# SparkFun-ESP8266-Development-Board.net
KiCad netlist of a schematic drawn in EAGLE
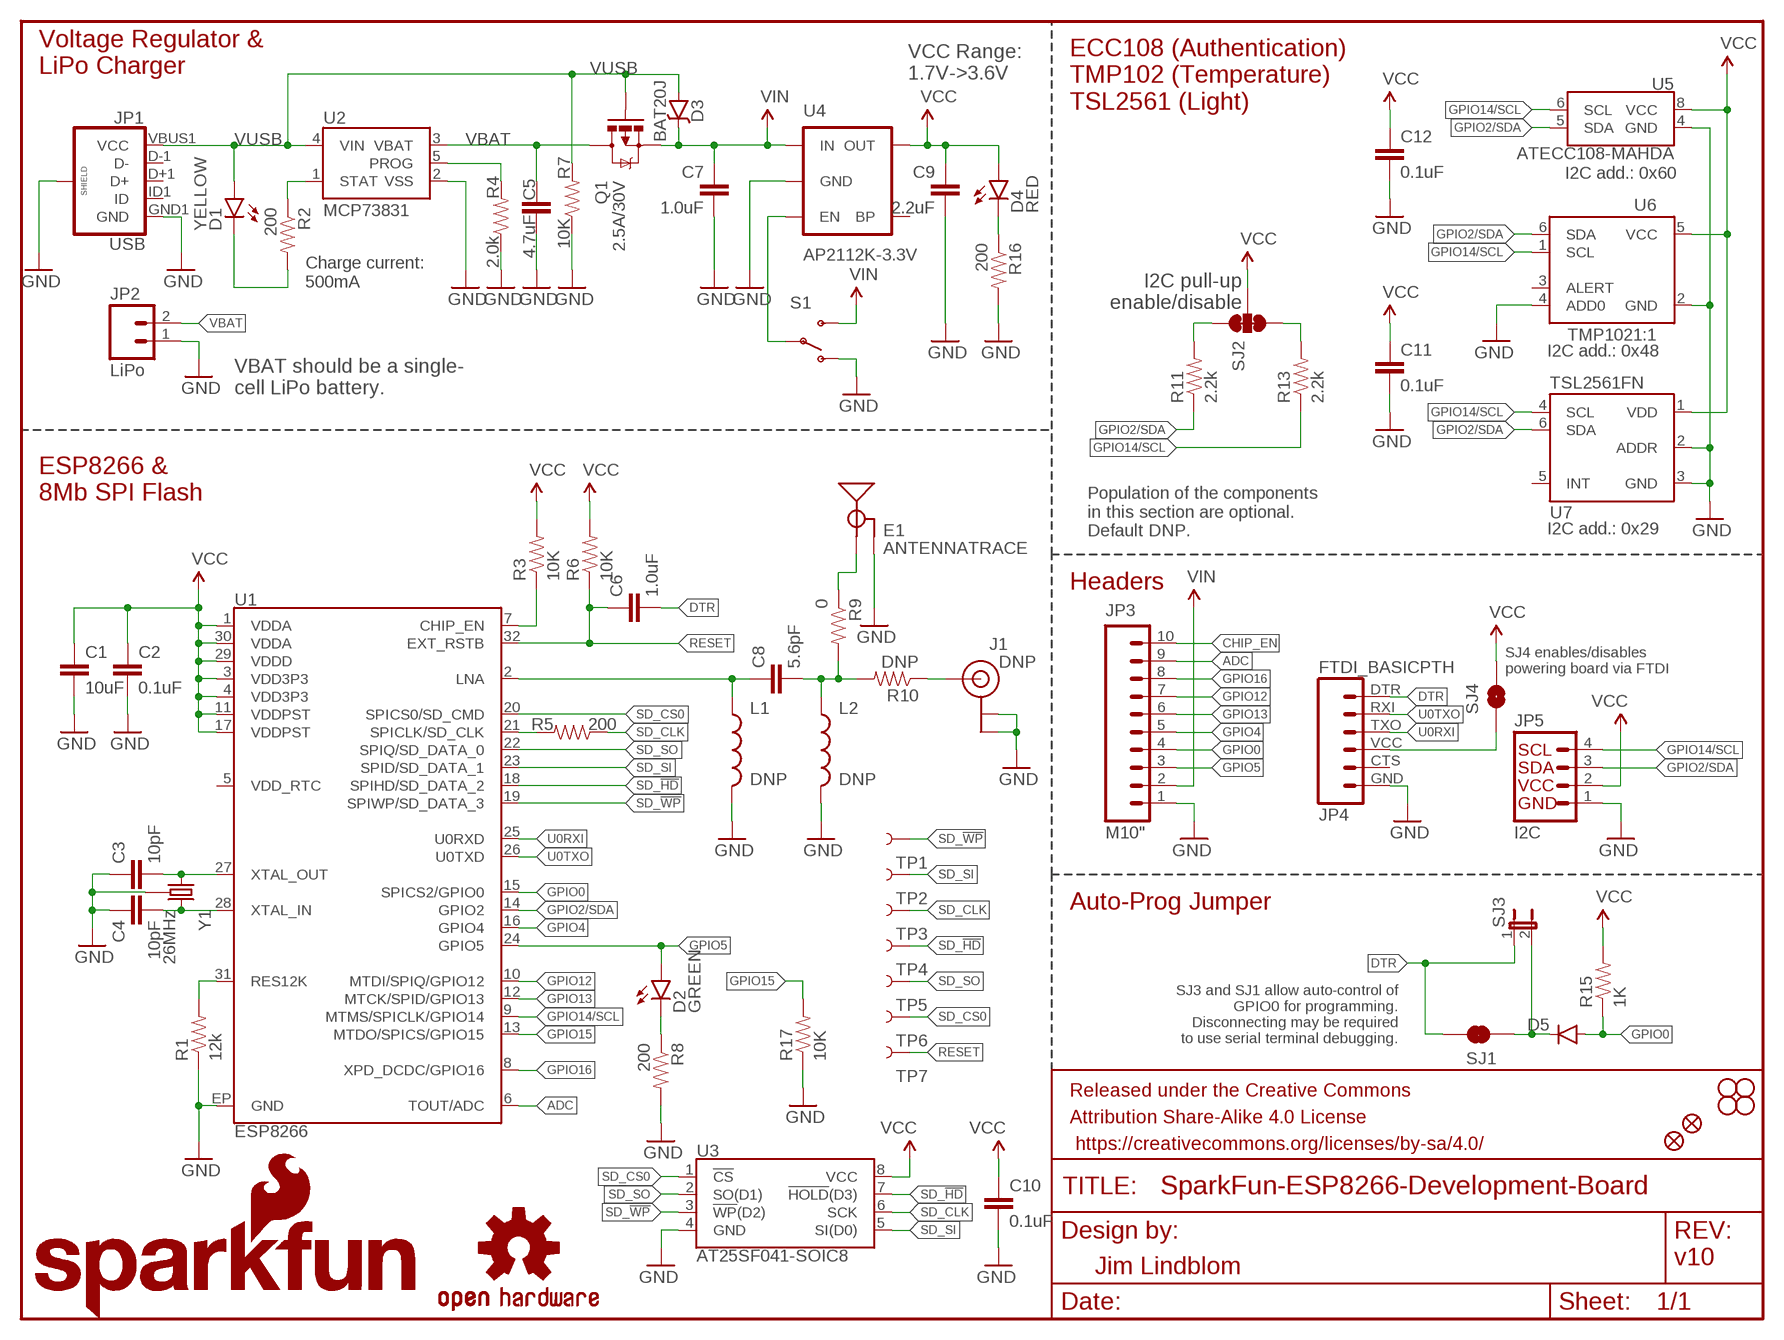
[diagram p0: schematic, sheet 1]

(export (version "E")
  (design (tool "Eeschema 10.0.6"))
  (components
    (comp (ref "C1")
      (value "10uF")
      (footprint "eagle-import:0603-CAP")
      (libsource (lib "eagle-import") (part "10UF-6.3V-20%(0603)"))
    )
    (comp (ref "C2")
      (value "0.1uF")
      (footprint "eagle-import:0603-CAP")
      (libsource (lib "eagle-import") (part "0.1UF-25V(+80/-20%)(0603)"))
    )
    (comp (ref "C3")
      (value "10pF")
      (footprint "eagle-import:0603-CAP")
      (libsource (lib "eagle-import") (part "10PF-50V-5%(0603)"))
    )
    (comp (ref "C4")
      (value "10pF")
      (footprint "eagle-import:0603-CAP")
      (libsource (lib "eagle-import") (part "10PF-50V-5%(0603)"))
    )
    (comp (ref "C5")
      (value "4.7uF")
      (footprint "eagle-import:0603-CAP")
      (libsource (lib "eagle-import") (part "4.7UF-6.3V-10%(0603)0603"))
    )
    (comp (ref "C6")
      (value "1.0uF")
      (footprint "eagle-import:0603-CAP")
      (libsource (lib "eagle-import") (part "1.0UF-16V-10%(0603)"))
    )
    (comp (ref "C7")
      (value "1.0uF")
      (footprint "eagle-import:0805")
      (libsource (lib "eagle-import") (part "1.0UF-25V-+80/-20(0805)"))
    )
    (comp (ref "C8")
      (value "5.6pF")
      (footprint "eagle-import:0603-CAP")
      (libsource (lib "eagle-import") (part "CAP0603-CAP"))
    )
    (comp (ref "C9")
      (value "2.2uF")
      (footprint "eagle-import:0603-CAP")
      (libsource (lib "eagle-import") (part "2.2UF-10V-20%(0603)"))
    )
    (comp (ref "C10")
      (value "0.1uF")
      (footprint "eagle-import:0603-CAP")
      (libsource (lib "eagle-import") (part "0.1UF-25V(+80/-20%)(0603)"))
    )
    (comp (ref "C11")
      (value "0.1uF")
      (footprint "eagle-import:0603-CAP")
      (libsource (lib "eagle-import") (part "0.1UF-25V(+80/-20%)(0603)"))
    )
    (comp (ref "C12")
      (value "0.1uF")
      (footprint "eagle-import:0603-CAP")
      (libsource (lib "eagle-import") (part "0.1UF-25V(+80/-20%)(0603)"))
    )
    (comp (ref "D1")
      (value "YELLOW")
      (footprint "eagle-import:LED-0603")
      (libsource (lib "eagle-import") (part "LED-YELLOW0603"))
    )
    (comp (ref "D2")
      (value "GREEN")
      (footprint "eagle-import:LED-0603")
      (libsource (lib "eagle-import") (part "LED-GREEN0603"))
    )
    (comp (ref "D3")
      (value "BAT20J")
      (footprint "eagle-import:SOD-323")
      (libsource (lib "eagle-import") (part "DIODE-SCHOTTKY-BAT20J"))
    )
    (comp (ref "D4")
      (value "RED")
      (footprint "eagle-import:LED-0603")
      (libsource (lib "eagle-import") (part "LED-RED0603"))
    )
    (comp (ref "D5")
      (value "DIODEBAS16")
      (footprint "eagle-import:SOD-323")
      (libsource (lib "eagle-import") (part "DIODEBAS16"))
    )
    (comp (ref "E1")
      (value "ANTENNATRACE")
      (footprint "eagle-import:TRACE_ANTENNA_2.4GHZ_25.7MM")
      (libsource (lib "eagle-import") (part "ANTENNATRACE"))
    )
    (comp (ref "FID1")
      (value "FIDUCIAL1X2")
      (footprint "eagle-import:FIDUCIAL-1X2")
      (libsource (lib "eagle-import") (part "FIDUCIAL1X2"))
    )
    (comp (ref "FID2")
      (value "FIDUCIAL1X2")
      (footprint "eagle-import:FIDUCIAL-1X2")
      (libsource (lib "eagle-import") (part "FIDUCIAL1X2"))
    )
    (comp (ref "FRAME1")
      (value "FRAME-LETTER")
      (footprint "eagle-import:CREATIVE_COMMONS")
      (libsource (lib "eagle-import") (part "FRAME-LETTER"))
    )
    (comp (ref "J1")
      (value "DNP")
      (footprint "eagle-import:U.FL")
      (libsource (lib "eagle-import") (part "U.FL"))
    )
    (comp (ref "JP1")
      (value "USB")
      (footprint "eagle-import:USB-B-MICRO-SMD_V03")
      (libsource (lib "eagle-import") (part "USB_MICROB_PLUGCONN-11752"))
    )
    (comp (ref "JP2")
      (value "LiPo")
      (footprint "eagle-import:JST-2-PTH")
      (libsource (lib "eagle-import") (part "M02JST-PTH-2"))
    )
    (comp (ref "JP3")
      (value "M10\"")
      (footprint "eagle-import:1X10")
      (libsource (lib "eagle-import") (part "M10{dblquote}"))
    )
    (comp (ref "JP4")
      (value "FTDI_BASICPTH")
      (footprint "eagle-import:FTDI_BASIC")
      (libsource (lib "eagle-import") (part "FTDI_BASICPTH"))
    )
    (comp (ref "JP5")
      (value "I2C")
      (footprint "eagle-import:1X04")
      (libsource (lib "eagle-import") (part "I2C_STANDARD"))
    )
    (comp (ref "L1")
      (value "DNP")
      (footprint "eagle-import:0603")
      (libsource (lib "eagle-import") (part "INDUCTOR0603"))
    )
    (comp (ref "L2")
      (value "DNP")
      (footprint "eagle-import:0603")
      (libsource (lib "eagle-import") (part "INDUCTOR0603"))
    )
    (comp (ref "LOGO1")
      (value "SFE_LOGO_NAME.2_INCH")
      (footprint "eagle-import:SFE_LOGO_NAME_.2")
      (libsource (lib "eagle-import") (part "SFE_LOGO_NAME.2_INCH"))
    )
    (comp (ref "LOGO3")
      (value "SFE_LOGO_FLAME.1_INCH")
      (footprint "eagle-import:SFE_LOGO_FLAME_.1")
      (libsource (lib "eagle-import") (part "SFE_LOGO_FLAME.1_INCH"))
    )
    (comp (ref "LOGO4")
      (value "OSHW-LOGOS")
      (footprint "eagle-import:OSHW-LOGO-S")
      (libsource (lib "eagle-import") (part "OSHW-LOGOS"))
    )
    (comp (ref "Q1")
      (value "2.5A/30V")
      (footprint "eagle-import:SOT23-3")
      (libsource (lib "eagle-import") (part "MOSFET-PCHANNELDMG2307L"))
    )
    (comp (ref "R1")
      (value "12k")
      (footprint "eagle-import:0603-RES")
      (libsource (lib "eagle-import") (part "12KOHM-1/10W-1%(0603)"))
    )
    (comp (ref "R2")
      (value "200")
      (footprint "eagle-import:0603-RES")
      (libsource (lib "eagle-import") (part "200OHM1/10W1%(0603)"))
    )
    (comp (ref "R3")
      (value "10K")
      (footprint "eagle-import:0603-RES")
      (libsource (lib "eagle-import") (part "10KOHM1/10W1%(0603)0603"))
    )
    (comp (ref "R4")
      (value "2.0k")
      (footprint "eagle-import:0603-RES")
      (libsource (lib "eagle-import") (part "2.0KOHM1/10W5%(0603)"))
    )
    (comp (ref "R5")
      (value "200")
      (footprint "eagle-import:0603-RES")
      (libsource (lib "eagle-import") (part "200OHM1/10W1%(0603)"))
    )
    (comp (ref "R6")
      (value "10K")
      (footprint "eagle-import:0603-RES")
      (libsource (lib "eagle-import") (part "10KOHM1/10W1%(0603)0603"))
    )
    (comp (ref "R7")
      (value "10K")
      (footprint "eagle-import:0603-RES")
      (libsource (lib "eagle-import") (part "10KOHM1/10W1%(0603)0603"))
    )
    (comp (ref "R8")
      (value "200")
      (footprint "eagle-import:0603-RES")
      (libsource (lib "eagle-import") (part "200OHM1/10W1%(0603)"))
    )
    (comp (ref "R9")
      (value "0")
      (footprint "eagle-import:0603")
      (libsource (lib "eagle-import") (part "0OHM1/10W5%(0603)"))
    )
    (comp (ref "R10")
      (value "DNP")
      (footprint "eagle-import:0603-RES")
      (libsource (lib "eagle-import") (part "RESISTOR0603-RES"))
    )
    (comp (ref "R11")
      (value "2.2k")
      (footprint "eagle-import:0603-RES")
      (libsource (lib "eagle-import") (part "2.2KOHM1/10W1%(0603)"))
    )
    (comp (ref "R13")
      (value "2.2k")
      (footprint "eagle-import:0603-RES")
      (libsource (lib "eagle-import") (part "2.2KOHM1/10W1%(0603)"))
    )
    (comp (ref "R15")
      (value "1K")
      (footprint "eagle-import:0603-RES")
      (libsource (lib "eagle-import") (part "1KOHM1/10W1%(0603)"))
    )
    (comp (ref "R16")
      (value "200")
      (footprint "eagle-import:0603-RES")
      (libsource (lib "eagle-import") (part "200OHM1/10W1%(0603)"))
    )
    (comp (ref "R17")
      (value "10K")
      (footprint "eagle-import:0603-RES")
      (libsource (lib "eagle-import") (part "10KOHM1/10W1%(0603)0603"))
    )
    (comp (ref "S1")
      (value "SWITCH-SPDT-SMD-A")
      (footprint "eagle-import:SWITCH-SPST-SMD-A")
      (libsource (lib "eagle-import") (part "SWITCH-SPDT-SMD-A"))
    )
    (comp (ref "SJ1")
      (value "JUMPER-PAD-2-NC_BY_TRACE")
      (footprint "eagle-import:PAD-JUMPER-2-NC_BY_TRACE_YES_SILK")
      (libsource (lib "eagle-import") (part "JUMPER-PAD-2-NC_BY_TRACE"))
    )
    (comp (ref "SJ2")
      (value "JUMPER-PAD-3-NC_BY_TRACE")
      (footprint "eagle-import:PAD-JUMPER-3-3OF3_NC_BY_TRACE_YES_SILK_FULL_BOX")
      (libsource (lib "eagle-import") (part "JUMPER-PAD-3-NC_BY_TRACE"))
    )
    (comp (ref "SJ3")
      (value "JUMPER-PTH-2-NC")
      (footprint "eagle-import:PTH-JUMPER-NC_BOTTOM_NO_SILK")
      (libsource (lib "eagle-import") (part "JUMPER-PTH-2-NC"))
    )
    (comp (ref "SJ4")
      (value "JUMPER-PAD-2-NOYES_SILK")
      (footprint "eagle-import:PAD-JUMPER-2-NO_YES_SILK")
      (libsource (lib "eagle-import") (part "JUMPER-PAD-2-NOYES_SILK"))
    )
    (comp (ref "STANDOFF1")
      (value "STAND-OFF")
      (footprint "eagle-import:STAND-OFF")
      (libsource (lib "eagle-import") (part "STAND-OFF"))
    )
    (comp (ref "STANDOFF2")
      (value "STAND-OFF")
      (footprint "eagle-import:STAND-OFF")
      (libsource (lib "eagle-import") (part "STAND-OFF"))
    )
    (comp (ref "STANDOFF3")
      (value "STAND-OFF")
      (footprint "eagle-import:STAND-OFF")
      (libsource (lib "eagle-import") (part "STAND-OFF"))
    )
    (comp (ref "STANDOFF4")
      (value "STAND-OFF")
      (footprint "eagle-import:STAND-OFF")
      (libsource (lib "eagle-import") (part "STAND-OFF"))
    )
    (comp (ref "TP1")
      (value "TEST-POINT3X5")
      (footprint "eagle-import:PAD.03X.05")
      (libsource (lib "eagle-import") (part "TEST-POINT3X5"))
    )
    (comp (ref "TP2")
      (value "TEST-POINT3X5")
      (footprint "eagle-import:PAD.03X.05")
      (libsource (lib "eagle-import") (part "TEST-POINT3X5"))
    )
    (comp (ref "TP3")
      (value "TEST-POINT3X5")
      (footprint "eagle-import:PAD.03X.05")
      (libsource (lib "eagle-import") (part "TEST-POINT3X5"))
    )
    (comp (ref "TP4")
      (value "TEST-POINT3X5")
      (footprint "eagle-import:PAD.03X.05")
      (libsource (lib "eagle-import") (part "TEST-POINT3X5"))
    )
    (comp (ref "TP5")
      (value "TEST-POINT3X5")
      (footprint "eagle-import:PAD.03X.05")
      (libsource (lib "eagle-import") (part "TEST-POINT3X5"))
    )
    (comp (ref "TP6")
      (value "TEST-POINT3X5")
      (footprint "eagle-import:PAD.03X.05")
      (libsource (lib "eagle-import") (part "TEST-POINT3X5"))
    )
    (comp (ref "TP7")
      (value "TEST-POINT3X5")
      (footprint "eagle-import:PAD.03X.05")
      (libsource (lib "eagle-import") (part "TEST-POINT3X5"))
    )
    (comp (ref "U1")
      (value "ESP8266")
      (footprint "eagle-import:QFN32")
      (libsource (lib "eagle-import") (part "ESP8266"))
    )
    (comp (ref "U2")
      (value "MCP73831")
      (footprint "eagle-import:SOT23-5")
      (libsource (lib "eagle-import") (part "MCP73831"))
    )
    (comp (ref "U3")
      (value "AT25SF041-SOIC8")
      (footprint "eagle-import:SO08")
      (libsource (lib "eagle-import") (part "AT25SF041-SOIC8"))
    )
    (comp (ref "U4")
      (value "AP2112K-3.3V")
      (footprint "eagle-import:SOT23-5")
      (libsource (lib "eagle-import") (part "V_REG_LDOSMD"))
    )
    (comp (ref "U5")
      (value "ATECC108-MAHDA")
      (footprint "eagle-import:UDFN8")
      (libsource (lib "eagle-import") (part "ATECC108-MAHDA"))
    )
    (comp (ref "U6")
      (value "TMP1021:1")
      (footprint "eagle-import:SOT563-2")
      (libsource (lib "eagle-import") (part "TMP1021{colon}1"))
    )
    (comp (ref "U7")
      (value "TSL2561FN")
      (footprint "eagle-import:FN-6")
      (libsource (lib "eagle-import") (part "TSL2561FN"))
    )
    (comp (ref "Y1")
      (value "26MHz")
      (footprint "eagle-import:CRYSTAL-SMD-3.2X2.5")
      (libsource (lib "eagle-import") (part "CRYSTAL-GROUNDED3.2X2.5"))
    )
  )
  (nets
    (net (code "1") (name "/SD_~{HD}") (class "Default")
      (node (ref "TP4") (pin "P$1") (pinfunction "1_P$1") (pintype "bidirectional"))
      (node (ref "U1") (pin "18") (pinfunction "SPIHD/SD_DATA_2_18") (pintype "bidirectional"))
      (node (ref "U3") (pin "7") (pinfunction "~{HOLD}(D3)_7") (pintype "bidirectional"))
    )
    (net (code "2") (name "/SD_~{WP}") (class "Default")
      (node (ref "TP1") (pin "P$1") (pinfunction "1_P$1") (pintype "bidirectional"))
      (node (ref "U1") (pin "19") (pinfunction "SPIWP/SD_DATA_3_19") (pintype "bidirectional"))
      (node (ref "U3") (pin "3") (pinfunction "~{WP}(D2)_3") (pintype "bidirectional"))
    )
    (net (code "3") (name "/VUSB") (class "Default")
      (node (ref "D1") (pin "A") (pinfunction "A_A") (pintype "passive"))
      (node (ref "D3") (pin "A") (pinfunction "A_A") (pintype "passive"))
      (node (ref "JP1") (pin "VBUS1") (pinfunction "VCC_VBUS1") (pintype "bidirectional"))
      (node (ref "Q1") (pin "1") (pinfunction "G_1") (pintype "passive"))
      (node (ref "R7") (pin "2") (pinfunction "2_2") (pintype "passive"))
      (node (ref "U2") (pin "4") (pinfunction "VIN_4") (pintype "power_in"))
    )
    (net (code "4") (name "ADC") (class "Default")
      (node (ref "JP3") (pin "9") (pinfunction "9_9") (pintype "passive"))
      (node (ref "U1") (pin "6") (pinfunction "TOUT/ADC_6") (pintype "bidirectional"))
    )
    (net (code "5") (name "CHIP_EN") (class "Default")
      (node (ref "JP3") (pin "10") (pinfunction "10_10") (pintype "passive"))
      (node (ref "R3") (pin "1") (pinfunction "1_1") (pintype "passive"))
      (node (ref "U1") (pin "7") (pinfunction "CHIP_EN_7") (pintype "bidirectional"))
    )
    (net (code "6") (name "DTR") (class "Default")
      (node (ref "C6") (pin "2") (pinfunction "2_2") (pintype "passive"))
      (node (ref "JP4") (pin "DTR") (pinfunction "1_DTR") (pintype "passive"))
      (node (ref "SJ1") (pin "2") (pinfunction "2_2") (pintype "passive"))
      (node (ref "SJ3") (pin "1") (pinfunction "1_1") (pintype "passive"))
    )
    (net (code "7") (name "GND") (class "Default")
      (node (ref "C1") (pin "2") (pinfunction "2_2") (pintype "passive"))
      (node (ref "C10") (pin "2") (pinfunction "2_2") (pintype "passive"))
      (node (ref "C11") (pin "2") (pinfunction "2_2") (pintype "passive"))
      (node (ref "C12") (pin "2") (pinfunction "2_2") (pintype "passive"))
      (node (ref "C2") (pin "2") (pinfunction "2_2") (pintype "passive"))
      (node (ref "C3") (pin "1") (pinfunction "1_1") (pintype "passive"))
      (node (ref "C4") (pin "1") (pinfunction "1_1") (pintype "passive"))
      (node (ref "C5") (pin "2") (pinfunction "2_2") (pintype "passive"))
      (node (ref "C7") (pin "2") (pinfunction "2_2") (pintype "passive"))
      (node (ref "C9") (pin "2") (pinfunction "2_2") (pintype "passive"))
      (node (ref "E1") (pin "GND") (pinfunction "GND_GND") (pintype "bidirectional"))
      (node (ref "E1") (pin "GND2") (pinfunction "GND_GND2") (pintype "bidirectional"))
      (node (ref "J1") (pin "P$1") (pinfunction "GND_P$1") (pintype "bidirectional"))
      (node (ref "J1") (pin "P$2") (pinfunction "GND_P$2") (pintype "bidirectional"))
      (node (ref "JP1") (pin "GND1") (pinfunction "GND_GND1") (pintype "bidirectional"))
      (node (ref "JP1") (pin "SHIELD1") (pinfunction "SHIELD_SHIELD1") (pintype "bidirectional"))
      (node (ref "JP1") (pin "SHIELD2") (pinfunction "SHIELD_SHIELD2") (pintype "bidirectional"))
      (node (ref "JP1") (pin "SHIELD3") (pinfunction "SHIELD_SHIELD3") (pintype "bidirectional"))
      (node (ref "JP2") (pin "1") (pinfunction "1_1") (pintype "passive"))
      (node (ref "JP3") (pin "1") (pinfunction "1_1") (pintype "passive"))
      (node (ref "JP4") (pin "GND") (pinfunction "6_GND") (pintype "passive"))
      (node (ref "JP5") (pin "1") (pinfunction "1_1") (pintype "passive"))
      (node (ref "L1") (pin "2") (pinfunction "2_2") (pintype "passive"))
      (node (ref "L2") (pin "2") (pinfunction "2_2") (pintype "passive"))
      (node (ref "R1") (pin "1") (pinfunction "1_1") (pintype "passive"))
      (node (ref "R16") (pin "2") (pinfunction "2_2") (pintype "passive"))
      (node (ref "R17") (pin "1") (pinfunction "1_1") (pintype "passive"))
      (node (ref "R4") (pin "1") (pinfunction "1_1") (pintype "passive"))
      (node (ref "R7") (pin "1") (pinfunction "1_1") (pintype "passive"))
      (node (ref "R8") (pin "2") (pinfunction "2_2") (pintype "passive"))
      (node (ref "S1") (pin "1") (pinfunction "O_1") (pintype "passive"))
      (node (ref "U1") (pin "EP") (pinfunction "GND_EP") (pintype "bidirectional"))
      (node (ref "U2") (pin "2") (pinfunction "VSS_2") (pintype "power_in"))
      (node (ref "U3") (pin "4") (pinfunction "GND_4") (pintype "bidirectional"))
      (node (ref "U4") (pin "2") (pinfunction "GND_2") (pintype "input"))
      (node (ref "U5") (pin "4") (pinfunction "GND_4") (pintype "bidirectional"))
      (node (ref "U6") (pin "2") (pinfunction "GND_2") (pintype "bidirectional"))
      (node (ref "U6") (pin "4") (pinfunction "ADD0_4") (pintype "bidirectional"))
      (node (ref "U7") (pin "2") (pinfunction "ADDR_2") (pintype "input"))
      (node (ref "U7") (pin "3") (pinfunction "GND_3") (pintype "power_in"))
      (node (ref "Y1") (pin "2") (pinfunction "GND_2") (pintype "passive"))
      (node (ref "Y1") (pin "4") (pinfunction "GND_4") (pintype "passive"))
    )
    (net (code "8") (name "GPIO0") (class "Default")
      (node (ref "D5") (pin "A") (pinfunction "A_A") (pintype "passive"))
      (node (ref "JP3") (pin "4") (pinfunction "4_4") (pintype "passive"))
      (node (ref "R15") (pin "1") (pinfunction "1_1") (pintype "passive"))
      (node (ref "U1") (pin "15") (pinfunction "SPICS2/GPIO0_15") (pintype "bidirectional"))
    )
    (net (code "9") (name "GPIO2{slash}SDA") (class "Default")
      (node (ref "JP5") (pin "3") (pinfunction "3_3") (pintype "passive"))
      (node (ref "R11") (pin "1") (pinfunction "1_1") (pintype "passive"))
      (node (ref "U1") (pin "14") (pinfunction "GPIO2_14") (pintype "bidirectional"))
      (node (ref "U5") (pin "5") (pinfunction "SDA_5") (pintype "bidirectional"))
      (node (ref "U6") (pin "6") (pinfunction "SDA_6") (pintype "bidirectional"))
      (node (ref "U7") (pin "6") (pinfunction "SDA_6") (pintype "bidirectional"))
    )
    (net (code "10") (name "GPIO4") (class "Default")
      (node (ref "JP3") (pin "5") (pinfunction "5_5") (pintype "passive"))
      (node (ref "U1") (pin "16") (pinfunction "GPIO4_16") (pintype "bidirectional"))
    )
    (net (code "11") (name "GPIO5") (class "Default")
      (node (ref "D2") (pin "A") (pinfunction "A_A") (pintype "passive"))
      (node (ref "JP3") (pin "3") (pinfunction "3_3") (pintype "passive"))
      (node (ref "U1") (pin "24") (pinfunction "GPIO5_24") (pintype "bidirectional"))
    )
    (net (code "12") (name "GPIO12") (class "Default")
      (node (ref "JP3") (pin "7") (pinfunction "7_7") (pintype "passive"))
      (node (ref "U1") (pin "10") (pinfunction "MTDI/SPIQ/GPIO12_10") (pintype "bidirectional"))
    )
    (net (code "13") (name "GPIO13") (class "Default")
      (node (ref "JP3") (pin "6") (pinfunction "6_6") (pintype "passive"))
      (node (ref "U1") (pin "12") (pinfunction "MTCK/SPID/GPIO13_12") (pintype "bidirectional"))
    )
    (net (code "14") (name "GPIO14{slash}SCL") (class "Default")
      (node (ref "JP5") (pin "4") (pinfunction "4_4") (pintype "passive"))
      (node (ref "R13") (pin "1") (pinfunction "1_1") (pintype "passive"))
      (node (ref "U1") (pin "9") (pinfunction "MTMS/SPICLK/GPIO14_9") (pintype "bidirectional"))
      (node (ref "U5") (pin "6") (pinfunction "SCL_6") (pintype "bidirectional"))
      (node (ref "U6") (pin "1") (pinfunction "SCL_1") (pintype "bidirectional"))
      (node (ref "U7") (pin "4") (pinfunction "SCL_4") (pintype "input"))
    )
    (net (code "15") (name "GPIO15") (class "Default")
      (node (ref "R17") (pin "2") (pinfunction "2_2") (pintype "passive"))
      (node (ref "U1") (pin "13") (pinfunction "MTDO/SPICS/GPIO15_13") (pintype "bidirectional"))
    )
    (net (code "16") (name "GPIO16") (class "Default")
      (node (ref "JP3") (pin "8") (pinfunction "8_8") (pintype "passive"))
      (node (ref "U1") (pin "8") (pinfunction "XPD_DCDC/GPIO16_8") (pintype "bidirectional"))
    )
    (net (code "17") (name "Net-(C8-Pad2)") (class "Default")
      (node (ref "C8") (pin "2") (pinfunction "2_2") (pintype "passive"))
      (node (ref "L2") (pin "1") (pinfunction "1_1") (pintype "passive"))
      (node (ref "R10") (pin "2") (pinfunction "2_2") (pintype "passive"))
      (node (ref "R9") (pin "2") (pinfunction "2_2") (pintype "passive"))
    )
    (net (code "18") (name "Net-(D1-PadC)") (class "Default")
      (node (ref "D1") (pin "C") (pinfunction "C_C") (pintype "passive"))
      (node (ref "R2") (pin "2") (pinfunction "2_2") (pintype "passive"))
    )
    (net (code "19") (name "Net-(D2-PadC)") (class "Default")
      (node (ref "D2") (pin "C") (pinfunction "C_C") (pintype "passive"))
      (node (ref "R8") (pin "1") (pinfunction "1_1") (pintype "passive"))
    )
    (net (code "20") (name "Net-(D4-PadC)") (class "Default")
      (node (ref "D4") (pin "C") (pinfunction "C_C") (pintype "passive"))
      (node (ref "R16") (pin "1") (pinfunction "1_1") (pintype "passive"))
    )
    (net (code "21") (name "Net-(D5-PadC)") (class "Default")
      (node (ref "D5") (pin "C") (pinfunction "C_C") (pintype "passive"))
      (node (ref "SJ1") (pin "1") (pinfunction "1_1") (pintype "passive"))
      (node (ref "SJ3") (pin "2") (pinfunction "2_2") (pintype "passive"))
    )
    (net (code "22") (name "Net-(E1-SIGNAL)") (class "Default")
      (node (ref "E1") (pin "ANT") (pinfunction "SIGNAL_ANT") (pintype "bidirectional"))
      (node (ref "R9") (pin "1") (pinfunction "1_1") (pintype "passive"))
    )
    (net (code "23") (name "Net-(J1-SIGNAL)") (class "Default")
      (node (ref "J1") (pin "P$3") (pinfunction "SIGNAL_P$3") (pintype "bidirectional"))
      (node (ref "R10") (pin "1") (pinfunction "1_1") (pintype "passive"))
    )
    (net (code "24") (name "Net-(JP4-4)") (class "Default")
      (node (ref "JP4") (pin "VCC") (pinfunction "4_VCC") (pintype "passive"))
      (node (ref "SJ4") (pin "1") (pinfunction "1_1") (pintype "passive"))
    )
    (net (code "25") (name "Net-(R11-Pad2)") (class "Default")
      (node (ref "R11") (pin "2") (pinfunction "2_2") (pintype "passive"))
      (node (ref "SJ2") (pin "1") (pinfunction "1_1") (pintype "passive"))
    )
    (net (code "26") (name "Net-(R13-Pad2)") (class "Default")
      (node (ref "R13") (pin "2") (pinfunction "2_2") (pintype "passive"))
      (node (ref "SJ2") (pin "3") (pinfunction "3_3") (pintype "passive"))
    )
    (net (code "27") (name "Net-(S1-P)") (class "Default")
      (node (ref "S1") (pin "2") (pinfunction "P_2") (pintype "passive"))
      (node (ref "U4") (pin "3") (pinfunction "EN_3") (pintype "input"))
    )
    (net (code "28") (name "Net-(U1-LNA)") (class "Default")
      (node (ref "C8") (pin "1") (pinfunction "1_1") (pintype "passive"))
      (node (ref "L1") (pin "1") (pinfunction "1_1") (pintype "passive"))
      (node (ref "U1") (pin "2") (pinfunction "LNA_2") (pintype "bidirectional"))
    )
    (net (code "29") (name "Net-(U1-RES12K)") (class "Default")
      (node (ref "R1") (pin "2") (pinfunction "2_2") (pintype "passive"))
      (node (ref "U1") (pin "31") (pinfunction "RES12K_31") (pintype "bidirectional"))
    )
    (net (code "30") (name "Net-(U1-SPICLK{slash}SD_CLK)") (class "Default")
      (node (ref "R5") (pin "2") (pinfunction "2_2") (pintype "passive"))
      (node (ref "U1") (pin "21") (pinfunction "SPICLK/SD_CLK_21") (pintype "bidirectional"))
    )
    (net (code "31") (name "Net-(U1-XTAL_IN)") (class "Default")
      (node (ref "C4") (pin "2") (pinfunction "2_2") (pintype "passive"))
      (node (ref "U1") (pin "28") (pinfunction "XTAL_IN_28") (pintype "bidirectional"))
      (node (ref "Y1") (pin "3") (pinfunction "2_3") (pintype "passive"))
    )
    (net (code "32") (name "Net-(U1-XTAL_OUT)") (class "Default")
      (node (ref "C3") (pin "2") (pinfunction "2_2") (pintype "passive"))
      (node (ref "U1") (pin "27") (pinfunction "XTAL_OUT_27") (pintype "bidirectional"))
      (node (ref "Y1") (pin "1") (pinfunction "1_1") (pintype "passive"))
    )
    (net (code "33") (name "Net-(U2-PROG)") (class "Default")
      (node (ref "R4") (pin "2") (pinfunction "2_2") (pintype "passive"))
      (node (ref "U2") (pin "5") (pinfunction "PROG_5") (pintype "input"))
    )
    (net (code "34") (name "Net-(U2-STAT)") (class "Default")
      (node (ref "R2") (pin "1") (pinfunction "1_1") (pintype "passive"))
      (node (ref "U2") (pin "1") (pinfunction "STAT_1") (pintype "output"))
    )
    (net (code "35") (name "RESET") (class "Default")
      (node (ref "C6") (pin "1") (pinfunction "1_1") (pintype "passive"))
      (node (ref "R6") (pin "1") (pinfunction "1_1") (pintype "passive"))
      (node (ref "TP7") (pin "P$1") (pinfunction "1_P$1") (pintype "bidirectional"))
      (node (ref "U1") (pin "32") (pinfunction "EXT_RSTB_32") (pintype "bidirectional"))
    )
    (net (code "36") (name "SD_CLK") (class "Default")
      (node (ref "R5") (pin "1") (pinfunction "1_1") (pintype "passive"))
      (node (ref "TP3") (pin "P$1") (pinfunction "1_P$1") (pintype "bidirectional"))
      (node (ref "U3") (pin "6") (pinfunction "SCK_6") (pintype "bidirectional"))
    )
    (net (code "37") (name "SD_CS0") (class "Default")
      (node (ref "TP6") (pin "P$1") (pinfunction "1_P$1") (pintype "bidirectional"))
      (node (ref "U1") (pin "20") (pinfunction "SPICS0/SD_CMD_20") (pintype "bidirectional"))
      (node (ref "U3") (pin "1") (pinfunction "~{CS}_1") (pintype "bidirectional"))
    )
    (net (code "38") (name "SD_SI") (class "Default")
      (node (ref "TP2") (pin "P$1") (pinfunction "1_P$1") (pintype "bidirectional"))
      (node (ref "U1") (pin "23") (pinfunction "SPID/SD_DATA_1_23") (pintype "bidirectional"))
      (node (ref "U3") (pin "5") (pinfunction "SI(D0)_5") (pintype "bidirectional"))
    )
    (net (code "39") (name "SD_SO") (class "Default")
      (node (ref "TP5") (pin "P$1") (pinfunction "1_P$1") (pintype "bidirectional"))
      (node (ref "U1") (pin "22") (pinfunction "SPIQ/SD_DATA_0_22") (pintype "bidirectional"))
      (node (ref "U3") (pin "2") (pinfunction "SO(D1)_2") (pintype "bidirectional"))
    )
    (net (code "40") (name "U0RXI") (class "Default")
      (node (ref "JP4") (pin "TXO") (pinfunction "3_TXO") (pintype "passive"))
      (node (ref "U1") (pin "25") (pinfunction "U0RXD_25") (pintype "bidirectional"))
    )
    (net (code "41") (name "U0TXO") (class "Default")
      (node (ref "JP4") (pin "RXI") (pinfunction "2_RXI") (pintype "passive"))
      (node (ref "U1") (pin "26") (pinfunction "U0TXD_26") (pintype "bidirectional"))
    )
    (net (code "42") (name "VBAT") (class "Default")
      (node (ref "C5") (pin "1") (pinfunction "1_1") (pintype "passive"))
      (node (ref "JP2") (pin "2") (pinfunction "2_2") (pintype "passive"))
      (node (ref "Q1") (pin "3") (pinfunction "D_3") (pintype "passive"))
      (node (ref "U2") (pin "3") (pinfunction "VBAT_3") (pintype "power_in"))
    )
    (net (code "43") (name "VCC") (class "Default")
      (node (ref "C1") (pin "1") (pinfunction "1_1") (pintype "passive"))
      (node (ref "C10") (pin "1") (pinfunction "1_1") (pintype "passive"))
      (node (ref "C11") (pin "1") (pinfunction "1_1") (pintype "passive"))
      (node (ref "C12") (pin "1") (pinfunction "1_1") (pintype "passive"))
      (node (ref "C2") (pin "1") (pinfunction "1_1") (pintype "passive"))
      (node (ref "C9") (pin "1") (pinfunction "1_1") (pintype "passive"))
      (node (ref "D4") (pin "A") (pinfunction "A_A") (pintype "passive"))
      (node (ref "JP5") (pin "2") (pinfunction "2_2") (pintype "passive"))
      (node (ref "R15") (pin "2") (pinfunction "2_2") (pintype "passive"))
      (node (ref "R3") (pin "2") (pinfunction "2_2") (pintype "passive"))
      (node (ref "R6") (pin "2") (pinfunction "2_2") (pintype "passive"))
      (node (ref "SJ2") (pin "2") (pinfunction "2_2") (pintype "passive"))
      (node (ref "SJ4") (pin "2") (pinfunction "2_2") (pintype "passive"))
      (node (ref "U1") (pin "1") (pinfunction "VDDA_1") (pintype "bidirectional"))
      (node (ref "U1") (pin "11") (pinfunction "VDDPST_11") (pintype "bidirectional"))
      (node (ref "U1") (pin "17") (pinfunction "VDDPST_17") (pintype "bidirectional"))
      (node (ref "U1") (pin "29") (pinfunction "VDDD_29") (pintype "bidirectional"))
      (node (ref "U1") (pin "3") (pinfunction "VDD3P3_3") (pintype "bidirectional"))
      (node (ref "U1") (pin "30") (pinfunction "VDDA_30") (pintype "bidirectional"))
      (node (ref "U1") (pin "4") (pinfunction "VDD3P3_4") (pintype "bidirectional"))
      (node (ref "U3") (pin "8") (pinfunction "VCC_8") (pintype "bidirectional"))
      (node (ref "U4") (pin "5") (pinfunction "OUT_5") (pintype "passive"))
      (node (ref "U5") (pin "8") (pinfunction "VCC_8") (pintype "bidirectional"))
      (node (ref "U6") (pin "5") (pinfunction "VCC_5") (pintype "bidirectional"))
      (node (ref "U7") (pin "1") (pinfunction "VDD_1") (pintype "power_in"))
    )
    (net (code "44") (name "VIN") (class "Default")
      (node (ref "C7") (pin "1") (pinfunction "1_1") (pintype "passive"))
      (node (ref "D3") (pin "C") (pinfunction "C_C") (pintype "passive"))
      (node (ref "JP3") (pin "2") (pinfunction "2_2") (pintype "passive"))
      (node (ref "Q1") (pin "2") (pinfunction "S_2") (pintype "passive"))
      (node (ref "S1") (pin "3") (pinfunction "S_3") (pintype "passive"))
      (node (ref "U4") (pin "1") (pinfunction "IN_1") (pintype "input"))
    )
    (net (code "45") (name "unconnected-(JP1-D+-PadD+1)") (class "Default")
      (node (ref "JP1") (pin "D+1") (pinfunction "D+_D+1") (pintype "bidirectional"))
    )
    (net (code "46") (name "unconnected-(JP1-D--PadD-1)") (class "Default")
      (node (ref "JP1") (pin "D-1") (pinfunction "D-_D-1") (pintype "bidirectional"))
    )
    (net (code "47") (name "unconnected-(JP1-ID-PadID1)") (class "Default")
      (node (ref "JP1") (pin "ID1") (pinfunction "ID_ID1") (pintype "bidirectional"))
    )
    (net (code "48") (name "unconnected-(JP4-5-PadCTS)") (class "Default")
      (node (ref "JP4") (pin "CTS") (pinfunction "5_CTS") (pintype "passive"))
    )
    (net (code "49") (name "unconnected-(U1-VDD_RTC-Pad5)") (class "Default")
      (node (ref "U1") (pin "5") (pinfunction "VDD_RTC_5") (pintype "bidirectional"))
    )
    (net (code "50") (name "unconnected-(U4-BP-Pad4)") (class "Default")
      (node (ref "U4") (pin "4") (pinfunction "BP_4") (pintype "input"))
    )
    (net (code "51") (name "unconnected-(U6-ALERT-Pad3)") (class "Default")
      (node (ref "U6") (pin "3") (pinfunction "ALERT_3") (pintype "bidirectional"))
    )
    (net (code "52") (name "unconnected-(U7-INT-Pad5)") (class "Default")
      (node (ref "U7") (pin "5") (pinfunction "INT_5") (pintype "output"))
    )
  )
)
